# CP2102N-Breakout_v10.net
KiCad netlist of a schematic drawn in EAGLE
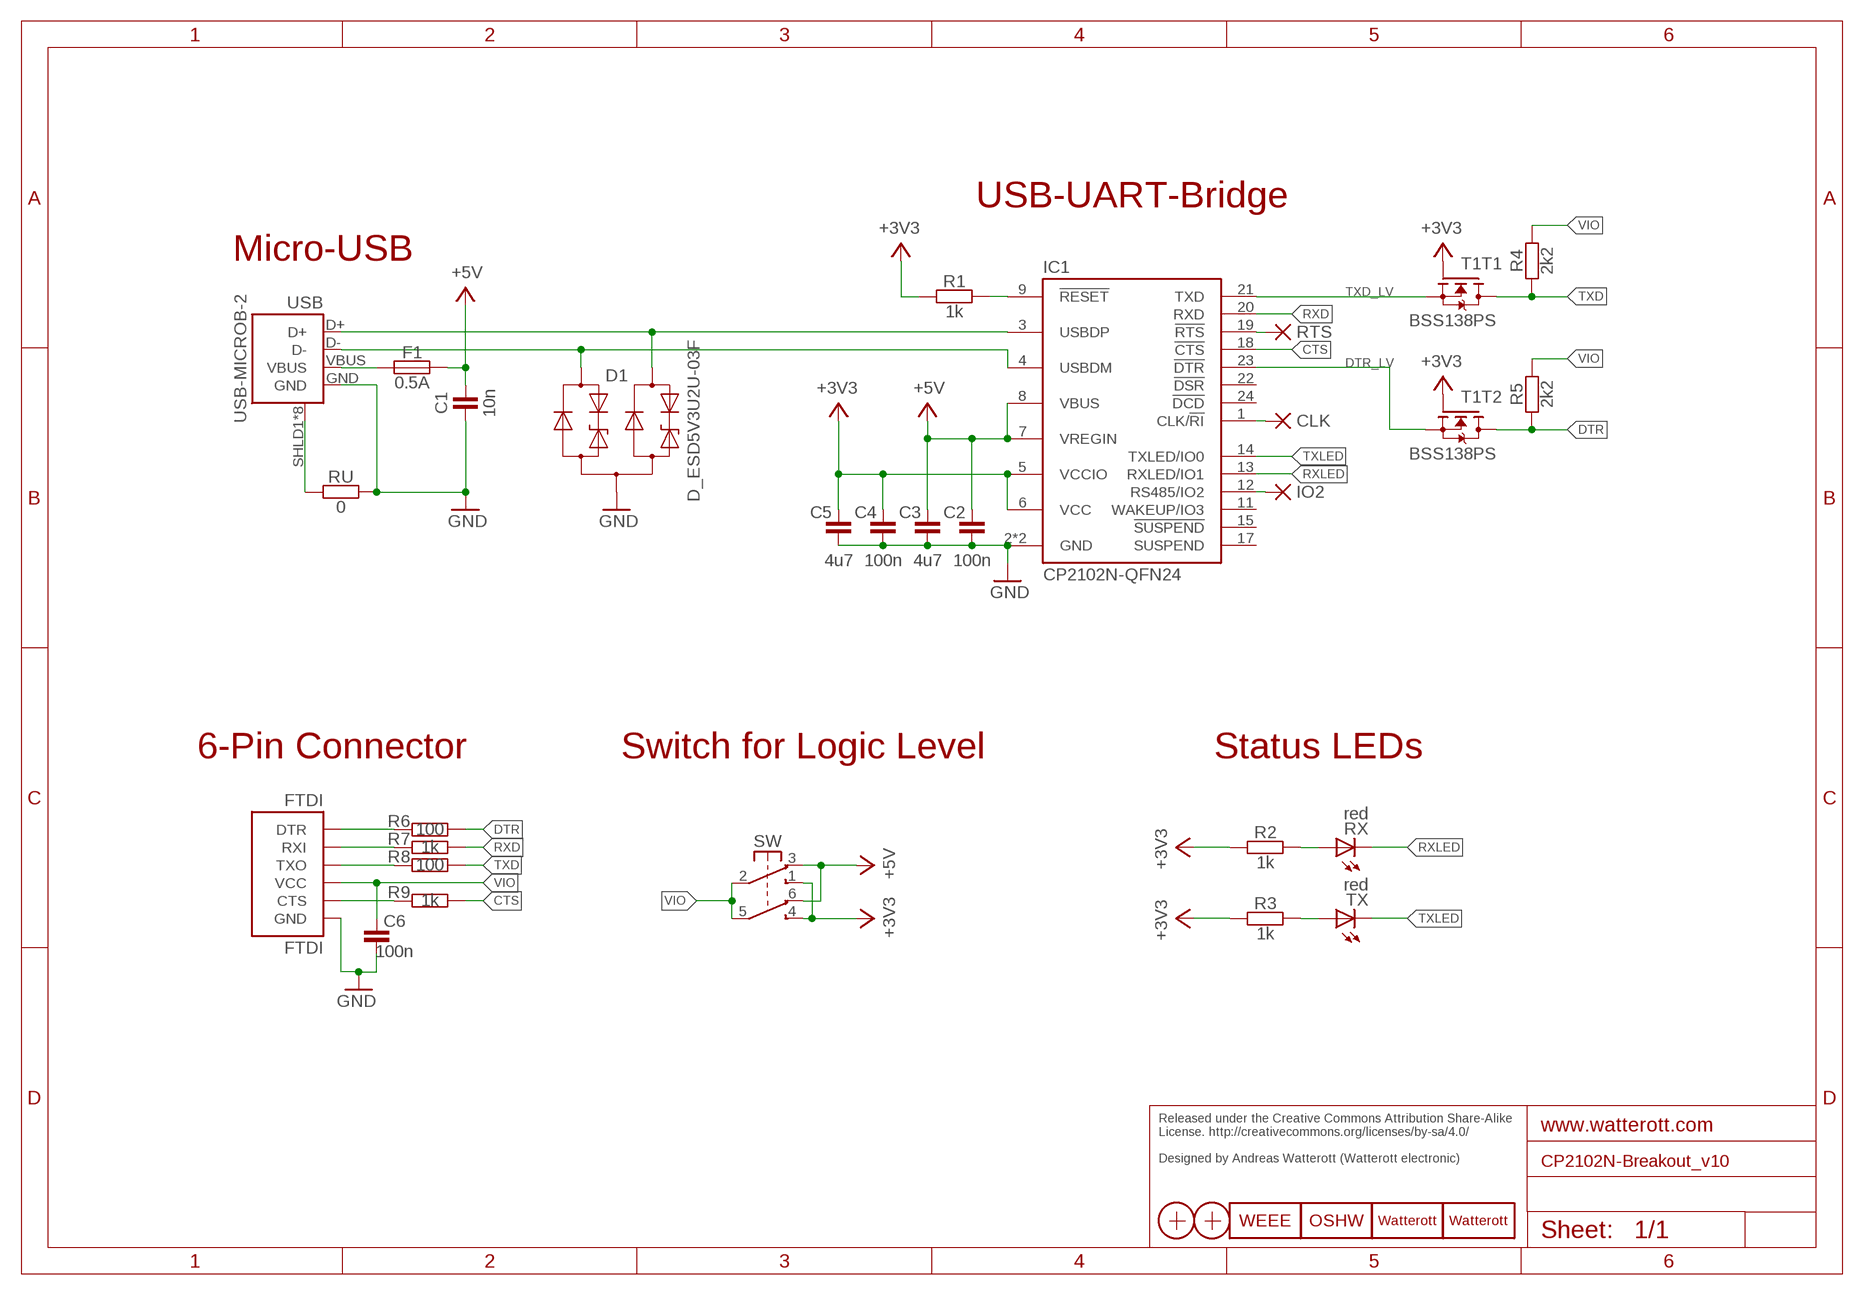
[diagram p0: schematic, sheet 1]

(export (version "E")
  (design (tool "Eeschema 10.0.6"))
  (components
    (comp (ref "C1")
      (value "10n")
      (footprint "eagle-import:C0402")
      (libsource (lib "eagle-import") (part "CAPACITOR-0402"))
    )
    (comp (ref "C2")
      (value "100n")
      (footprint "eagle-import:C0402")
      (libsource (lib "eagle-import") (part "CAPACITOR-0402"))
    )
    (comp (ref "C3")
      (value "4u7")
      (footprint "eagle-import:C0603")
      (libsource (lib "eagle-import") (part "CAPACITOR-0603"))
    )
    (comp (ref "C4")
      (value "100n")
      (footprint "eagle-import:C0402")
      (libsource (lib "eagle-import") (part "CAPACITOR-0402"))
    )
    (comp (ref "C5")
      (value "4u7")
      (footprint "eagle-import:C0603")
      (libsource (lib "eagle-import") (part "CAPACITOR-0603"))
    )
    (comp (ref "C6")
      (value "100n")
      (footprint "eagle-import:C0402")
      (libsource (lib "eagle-import") (part "CAPACITOR-0402"))
    )
    (comp (ref "CLK")
      (value "PAD-0.5_NC")
      (footprint "eagle-import:PAD-0.5_NC")
      (libsource (lib "eagle-import") (part "PAD-0.5_NC"))
    )
    (comp (ref "D1")
      (value "D_ESD5V3U2U-03F")
      (footprint "eagle-import:SOT723")
      (libsource (lib "eagle-import") (part "D_ESD5V3U2U-03F"))
    )
    (comp (ref "F1")
      (value "0.5A")
      (footprint "eagle-import:C0805")
      (libsource (lib "eagle-import") (part "FUSE-0805"))
    )
    (comp (ref "FTDI")
      (value "FTDI")
      (footprint "eagle-import:FTDI")
      (libsource (lib "eagle-import") (part "FTDI"))
    )
    (comp (ref "IC1")
      (value "CP2102N-QFN24")
      (footprint "eagle-import:QFN24-PAD")
      (libsource (lib "eagle-import") (part "CP2102N-QFN24"))
    )
    (comp (ref "IO2")
      (value "PAD-0.5_NC")
      (footprint "eagle-import:PAD-0.5_NC")
      (libsource (lib "eagle-import") (part "PAD-0.5_NC"))
    )
    (comp (ref "LOGO1")
      (value "WEEE_LOGO-S")
      (footprint "eagle-import:WEEE_TPLAC_S")
      (libsource (lib "eagle-import") (part "WEEE_LOGO-S"))
    )
    (comp (ref "LOGO2")
      (value "OSHW_LOGOX0070")
      (footprint "eagle-import:OSHW_6X70")
      (libsource (lib "eagle-import") (part "OSHW_LOGOX0070"))
    )
    (comp (ref "LOGO3")
      (value "LOGO-S_PLACE_S")
      (footprint "eagle-import:SPARK_TPLACE_S")
      (libsource (lib "eagle-import") (part "LOGO-S_PLACE_S"))
    )
    (comp (ref "LOGO4")
      (value "LOGO-S_PLACE_M")
      (footprint "eagle-import:SPARK_TPLACE_M")
      (libsource (lib "eagle-import") (part "LOGO-S_PLACE_M"))
    )
    (comp (ref "R1")
      (value "1k")
      (footprint "eagle-import:C0402")
      (libsource (lib "eagle-import") (part "RESISTOR-0402"))
    )
    (comp (ref "R2")
      (value "1k")
      (footprint "eagle-import:C0402")
      (libsource (lib "eagle-import") (part "RESISTOR-0402"))
    )
    (comp (ref "R3")
      (value "1k")
      (footprint "eagle-import:C0402")
      (libsource (lib "eagle-import") (part "RESISTOR-0402"))
    )
    (comp (ref "R4")
      (value "2k2")
      (footprint "eagle-import:C0402")
      (libsource (lib "eagle-import") (part "RESISTOR-0402"))
    )
    (comp (ref "R5")
      (value "2k2")
      (footprint "eagle-import:C0402")
      (libsource (lib "eagle-import") (part "RESISTOR-0402"))
    )
    (comp (ref "R6")
      (value "100")
      (footprint "eagle-import:C0402")
      (libsource (lib "eagle-import") (part "RESISTOR-0402"))
    )
    (comp (ref "R7")
      (value "1k")
      (footprint "eagle-import:C0402")
      (libsource (lib "eagle-import") (part "RESISTOR-0402"))
    )
    (comp (ref "R8")
      (value "100")
      (footprint "eagle-import:C0402")
      (libsource (lib "eagle-import") (part "RESISTOR-0402"))
    )
    (comp (ref "R9")
      (value "1k")
      (footprint "eagle-import:C0402")
      (libsource (lib "eagle-import") (part "RESISTOR-0402"))
    )
    (comp (ref "RTS")
      (value "PAD-0.5_NC")
      (footprint "eagle-import:PAD-0.5_NC")
      (libsource (lib "eagle-import") (part "PAD-0.5_NC"))
    )
    (comp (ref "RU")
      (value "0")
      (footprint "eagle-import:C0402")
      (libsource (lib "eagle-import") (part "RESISTOR-0402"))
    )
    (comp (ref "RX")
      (value "red")
      (footprint "eagle-import:C0603")
      (libsource (lib "eagle-import") (part "LED-0603"))
    )
    (comp (ref "SW")
      (value "SW-2UM-CUS22B")
      (footprint "eagle-import:CUS22B")
      (libsource (lib "eagle-import") (part "SW-2UM-CUS22B"))
    )
    (comp (ref "T1")
      (value "BSS138PS")
      (footprint "eagle-import:SOT363")
      (libsource (lib "eagle-import") (part "BSS138PS"))
    )
    (comp (ref "TX")
      (value "red")
      (footprint "eagle-import:C0603")
      (libsource (lib "eagle-import") (part "LED-0603"))
    )
    (comp (ref "USB")
      (value "USB-MICROB-2")
      (footprint "eagle-import:USB-MICROB-10118194")
      (libsource (lib "eagle-import") (part "USB-MICROB-2"))
    )
    (comp (ref "X1")
      (value "PASSER-07")
      (footprint "eagle-import:PASSER_07MM")
      (libsource (lib "eagle-import") (part "PASSER-07"))
    )
    (comp (ref "X2")
      (value "PASSER-07")
      (footprint "eagle-import:PASSER_07MM")
      (libsource (lib "eagle-import") (part "PASSER-07"))
    )
  )
  (nets
    (net (code "1") (name "+3V3") (class "Default")
      (node (ref "C4") (pin "2") (pinfunction "2_2") (pintype "passive"))
      (node (ref "C5") (pin "2") (pinfunction "2_2") (pintype "passive"))
      (node (ref "IC1") (pin "5") (pinfunction "VCCIO_5") (pintype "power_in"))
      (node (ref "IC1") (pin "6") (pinfunction "VCC_6") (pintype "power_in"))
      (node (ref "R1") (pin "1") (pinfunction "1_1") (pintype "passive"))
      (node (ref "R2") (pin "1") (pinfunction "1_1") (pintype "passive"))
      (node (ref "R3") (pin "1") (pinfunction "1_1") (pintype "passive"))
      (node (ref "SW") (pin "1") (pinfunction "S1_1") (pintype "passive"))
      (node (ref "SW") (pin "4") (pinfunction "S2_4") (pintype "passive"))
      (node (ref "T1") (pin "2") (pinfunction "G_2") (pintype "passive"))
      (node (ref "T1") (pin "5") (pinfunction "G_5") (pintype "passive"))
    )
    (net (code "2") (name "+5V") (class "Default")
      (node (ref "C1") (pin "2") (pinfunction "2_2") (pintype "passive"))
      (node (ref "C2") (pin "2") (pinfunction "2_2") (pintype "passive"))
      (node (ref "C3") (pin "2") (pinfunction "2_2") (pintype "passive"))
      (node (ref "F1") (pin "2") (pinfunction "2_2") (pintype "passive"))
      (node (ref "IC1") (pin "7") (pinfunction "VREGIN_7") (pintype "power_in"))
      (node (ref "IC1") (pin "8") (pinfunction "VBUS_8") (pintype "power_in"))
      (node (ref "SW") (pin "3") (pinfunction "O1_3") (pintype "passive"))
      (node (ref "SW") (pin "6") (pinfunction "O2_6") (pintype "passive"))
    )
    (net (code "3") (name "/DTR_LV") (class "Default")
      (node (ref "IC1") (pin "23") (pinfunction "~{DTR}_23") (pintype "bidirectional"))
      (node (ref "T1") (pin "4") (pinfunction "S_4") (pintype "passive"))
    )
    (net (code "4") (name "/TXD_LV") (class "Default")
      (node (ref "IC1") (pin "21") (pinfunction "TXD_21") (pintype "bidirectional"))
      (node (ref "T1") (pin "1") (pinfunction "S_1") (pintype "passive"))
    )
    (net (code "5") (name "CTS") (class "Default")
      (node (ref "IC1") (pin "18") (pinfunction "~{CTS}_18") (pintype "bidirectional"))
      (node (ref "R9") (pin "1") (pinfunction "1_1") (pintype "passive"))
    )
    (net (code "6") (name "DTR") (class "Default")
      (node (ref "R5") (pin "1") (pinfunction "1_1") (pintype "passive"))
      (node (ref "R6") (pin "1") (pinfunction "1_1") (pintype "passive"))
      (node (ref "T1") (pin "3") (pinfunction "D_3") (pintype "passive"))
    )
    (net (code "7") (name "GND") (class "Default")
      (node (ref "C1") (pin "1") (pinfunction "1_1") (pintype "passive"))
      (node (ref "C2") (pin "1") (pinfunction "1_1") (pintype "passive"))
      (node (ref "C3") (pin "1") (pinfunction "1_1") (pintype "passive"))
      (node (ref "C4") (pin "1") (pinfunction "1_1") (pintype "passive"))
      (node (ref "C5") (pin "1") (pinfunction "1_1") (pintype "passive"))
      (node (ref "C6") (pin "1") (pinfunction "1_1") (pintype "passive"))
      (node (ref "D1") (pin "3") (pinfunction "A_3") (pintype "passive"))
      (node (ref "FTDI") (pin "1-GND") (pinfunction "GND_1-GND") (pintype "power_in"))
      (node (ref "IC1") (pin "2") (pinfunction "GND_2") (pintype "power_in"))
      (node (ref "IC1") (pin "TP") (pinfunction "GND_TP") (pintype "power_in"))
      (node (ref "RU") (pin "2") (pinfunction "2_2") (pintype "passive"))
      (node (ref "USB") (pin "GND") (pinfunction "GND_GND") (pintype "power_in"))
    )
    (net (code "8") (name "Net-(CLK-P)") (class "Default")
      (node (ref "CLK") (pin "1") (pinfunction "P_1") (pintype "passive"))
      (node (ref "IC1") (pin "1") (pinfunction "CLK/~{RI}_1") (pintype "bidirectional"))
    )
    (net (code "9") (name "Net-(D1-C1)") (class "Default")
      (node (ref "D1") (pin "1") (pinfunction "C1_1") (pintype "passive"))
      (node (ref "IC1") (pin "4") (pinfunction "USBDM_4") (pintype "bidirectional"))
      (node (ref "USB") (pin "D-") (pinfunction "D-_D-") (pintype "bidirectional"))
    )
    (net (code "10") (name "Net-(D1-C2)") (class "Default")
      (node (ref "D1") (pin "2") (pinfunction "C2_2") (pintype "passive"))
      (node (ref "IC1") (pin "3") (pinfunction "USBDP_3") (pintype "bidirectional"))
      (node (ref "USB") (pin "D+") (pinfunction "D+_D+") (pintype "bidirectional"))
    )
    (net (code "11") (name "Net-(F1-Pad1)") (class "Default")
      (node (ref "F1") (pin "1") (pinfunction "1_1") (pintype "passive"))
      (node (ref "USB") (pin "VBUS") (pinfunction "VBUS_VBUS") (pintype "power_in"))
    )
    (net (code "12") (name "Net-(FTDI-CTS)") (class "Default")
      (node (ref "FTDI") (pin "2-CTS") (pinfunction "CTS_2-CTS") (pintype "bidirectional"))
      (node (ref "R9") (pin "2") (pinfunction "2_2") (pintype "passive"))
    )
    (net (code "13") (name "Net-(FTDI-DTR)") (class "Default")
      (node (ref "FTDI") (pin "6-DTR") (pinfunction "DTR_6-DTR") (pintype "bidirectional"))
      (node (ref "R6") (pin "2") (pinfunction "2_2") (pintype "passive"))
    )
    (net (code "14") (name "Net-(FTDI-RXI)") (class "Default")
      (node (ref "FTDI") (pin "5-RXI") (pinfunction "RXI_5-RXI") (pintype "bidirectional"))
      (node (ref "R7") (pin "2") (pinfunction "2_2") (pintype "passive"))
    )
    (net (code "15") (name "Net-(FTDI-TXO)") (class "Default")
      (node (ref "FTDI") (pin "4-TXO") (pinfunction "TXO_4-TXO") (pintype "bidirectional"))
      (node (ref "R8") (pin "2") (pinfunction "2_2") (pintype "passive"))
    )
    (net (code "16") (name "Net-(IC1-RS485{slash}IO2)") (class "Default")
      (node (ref "IC1") (pin "12") (pinfunction "RS485/IO2_12") (pintype "bidirectional"))
      (node (ref "IO2") (pin "1") (pinfunction "P_1") (pintype "passive"))
    )
    (net (code "17") (name "Net-(IC1-~{RESET})") (class "Default")
      (node (ref "IC1") (pin "9") (pinfunction "~{RESET}_9") (pintype "bidirectional"))
      (node (ref "R1") (pin "2") (pinfunction "2_2") (pintype "passive"))
    )
    (net (code "18") (name "Net-(IC1-~{RTS})") (class "Default")
      (node (ref "IC1") (pin "19") (pinfunction "~{RTS}_19") (pintype "bidirectional"))
      (node (ref "RTS") (pin "1") (pinfunction "P_1") (pintype "passive"))
    )
    (net (code "19") (name "Net-(R2-Pad2)") (class "Default")
      (node (ref "R2") (pin "2") (pinfunction "2_2") (pintype "passive"))
      (node (ref "RX") (pin "A") (pinfunction "A_A") (pintype "passive"))
    )
    (net (code "20") (name "Net-(R3-Pad2)") (class "Default")
      (node (ref "R3") (pin "2") (pinfunction "2_2") (pintype "passive"))
      (node (ref "TX") (pin "A") (pinfunction "A_A") (pintype "passive"))
    )
    (net (code "21") (name "Net-(RU-Pad1)") (class "Default")
      (node (ref "RU") (pin "1") (pinfunction "1_1") (pintype "passive"))
      (node (ref "USB") (pin "SHLD1") (pinfunction "SHIELD_SHLD1") (pintype "passive"))
      (node (ref "USB") (pin "SHLD2") (pinfunction "SHIELD_SHLD2") (pintype "passive"))
      (node (ref "USB") (pin "SHLD3") (pinfunction "SHIELD_SHLD3") (pintype "passive"))
      (node (ref "USB") (pin "SHLD4") (pinfunction "SHIELD_SHLD4") (pintype "passive"))
      (node (ref "USB") (pin "SHLD5") (pinfunction "SHIELD_SHLD5") (pintype "passive"))
      (node (ref "USB") (pin "SHLD6") (pinfunction "SHIELD_SHLD6") (pintype "passive"))
      (node (ref "USB") (pin "SHLD7") (pinfunction "SHIELD_SHLD7") (pintype "passive"))
      (node (ref "USB") (pin "SHLD8") (pinfunction "SHIELD_SHLD8") (pintype "passive"))
    )
    (net (code "22") (name "RXD") (class "Default")
      (node (ref "IC1") (pin "20") (pinfunction "RXD_20") (pintype "bidirectional"))
      (node (ref "R7") (pin "1") (pinfunction "1_1") (pintype "passive"))
    )
    (net (code "23") (name "RXLED") (class "Default")
      (node (ref "IC1") (pin "13") (pinfunction "RXLED/IO1_13") (pintype "bidirectional"))
      (node (ref "RX") (pin "C") (pinfunction "C_C") (pintype "passive"))
    )
    (net (code "24") (name "TXD") (class "Default")
      (node (ref "R4") (pin "1") (pinfunction "1_1") (pintype "passive"))
      (node (ref "R8") (pin "1") (pinfunction "1_1") (pintype "passive"))
      (node (ref "T1") (pin "6") (pinfunction "D_6") (pintype "passive"))
    )
    (net (code "25") (name "TXLED") (class "Default")
      (node (ref "IC1") (pin "14") (pinfunction "TXLED/IO0_14") (pintype "bidirectional"))
      (node (ref "TX") (pin "C") (pinfunction "C_C") (pintype "passive"))
    )
    (net (code "26") (name "VIO") (class "Default")
      (node (ref "C6") (pin "2") (pinfunction "2_2") (pintype "passive"))
      (node (ref "FTDI") (pin "3-VCC") (pinfunction "VCC_3-VCC") (pintype "power_in"))
      (node (ref "R4") (pin "2") (pinfunction "2_2") (pintype "passive"))
      (node (ref "R5") (pin "2") (pinfunction "2_2") (pintype "passive"))
      (node (ref "SW") (pin "2") (pinfunction "P1_2") (pintype "passive"))
      (node (ref "SW") (pin "5") (pinfunction "P2_5") (pintype "passive"))
    )
    (net (code "27") (name "unconnected-(IC1-SUSPEND-Pad17)") (class "Default")
      (node (ref "IC1") (pin "17") (pinfunction "SUSPEND_17") (pintype "bidirectional"))
    )
    (net (code "28") (name "unconnected-(IC1-WAKEUP{slash}IO3-Pad11)") (class "Default")
      (node (ref "IC1") (pin "11") (pinfunction "WAKEUP/IO3_11") (pintype "bidirectional"))
    )
    (net (code "29") (name "unconnected-(IC1-~{DCD}-Pad24)") (class "Default")
      (node (ref "IC1") (pin "24") (pinfunction "~{DCD}_24") (pintype "bidirectional"))
    )
    (net (code "30") (name "unconnected-(IC1-~{DSR}-Pad22)") (class "Default")
      (node (ref "IC1") (pin "22") (pinfunction "~{DSR}_22") (pintype "bidirectional"))
    )
    (net (code "31") (name "unconnected-(IC1-~{SUSPEND}-Pad15)") (class "Default")
      (node (ref "IC1") (pin "15") (pinfunction "~{SUSPEND}_15") (pintype "bidirectional"))
    )
  )
)
